# MotionBoard_Rev_C-old-sd.net
KiCad netlist of a schematic drawn in EAGLE
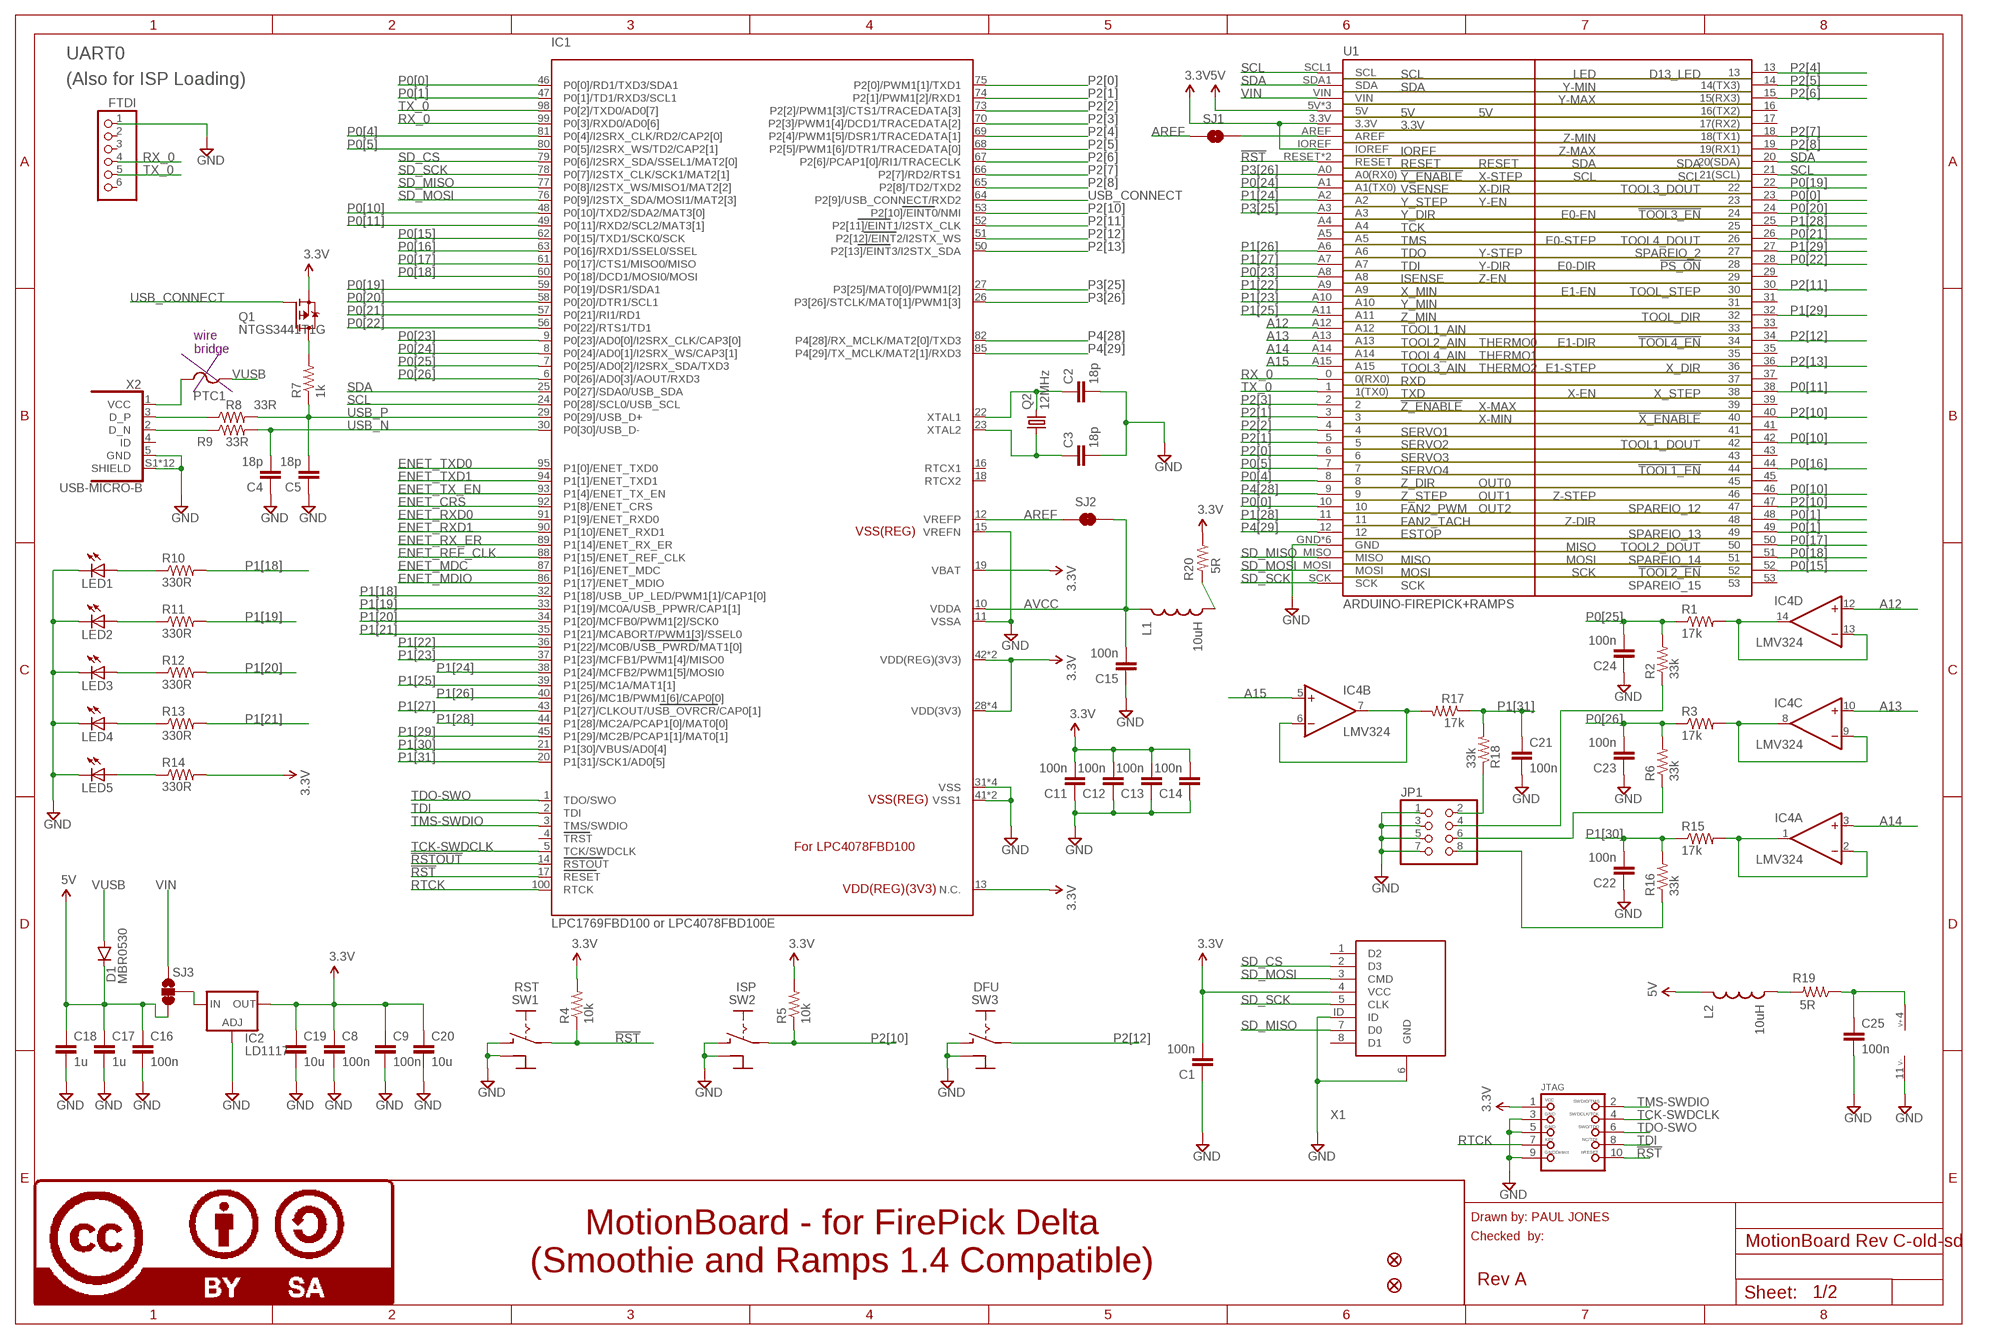
[diagram p0: schematic, sheet 1]
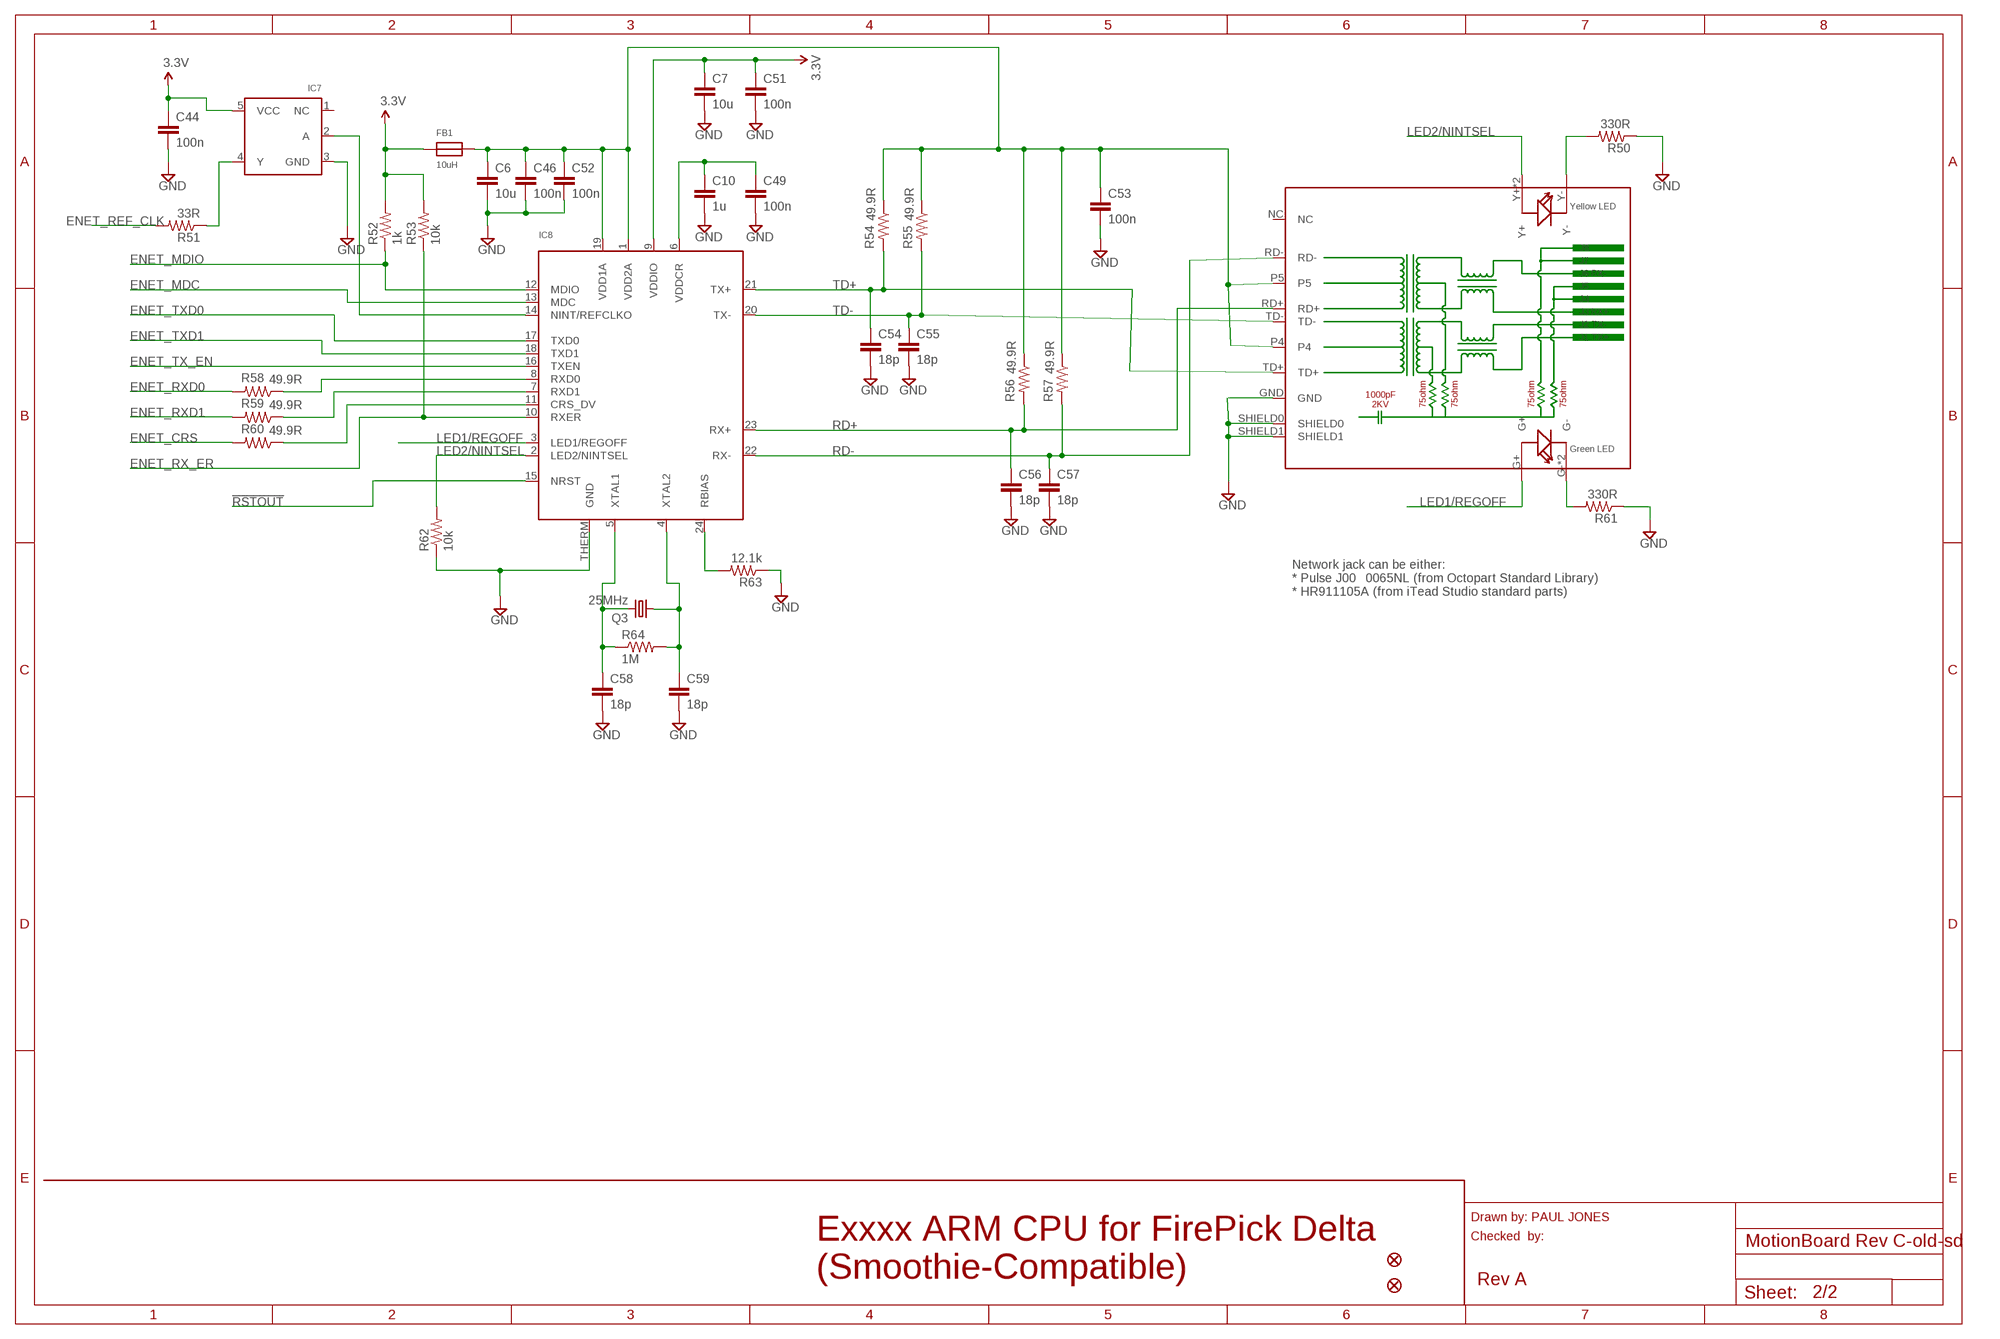
[diagram p1: schematic, sheet 2]

(export (version "E")
  (design (tool "Eeschema 10.0.6"))
  (components
    (comp (ref "C6")
      (value "10u")
      (footprint "eagle-import:0603")
      (libsource (lib "eagle-import") (part "CAP0603"))
    )
    (comp (ref "C7")
      (value "10u")
      (footprint "eagle-import:0603")
      (libsource (lib "eagle-import") (part "CAP0603"))
    )
    (comp (ref "C10")
      (value "1u")
      (footprint "eagle-import:0603")
      (libsource (lib "eagle-import") (part "CAP0603"))
    )
    (comp (ref "C44")
      (value "100n")
      (footprint "eagle-import:0603")
      (libsource (lib "eagle-import") (part "CAP0603"))
    )
    (comp (ref "C46")
      (value "100n")
      (footprint "eagle-import:0603")
      (libsource (lib "eagle-import") (part "CAP0603"))
    )
    (comp (ref "C49")
      (value "100n")
      (footprint "eagle-import:0603")
      (libsource (lib "eagle-import") (part "CAP0603"))
    )
    (comp (ref "C51")
      (value "100n")
      (footprint "eagle-import:0603")
      (libsource (lib "eagle-import") (part "CAP0603"))
    )
    (comp (ref "C52")
      (value "100n")
      (footprint "eagle-import:0603")
      (libsource (lib "eagle-import") (part "CAP0603"))
    )
    (comp (ref "C53")
      (value "100n")
      (footprint "eagle-import:0603")
      (libsource (lib "eagle-import") (part "CAP0603"))
    )
    (comp (ref "C54")
      (value "18p")
      (footprint "eagle-import:0603")
      (libsource (lib "eagle-import") (part "CAP0603"))
    )
    (comp (ref "C55")
      (value "18p")
      (footprint "eagle-import:0603")
      (libsource (lib "eagle-import") (part "CAP0603"))
    )
    (comp (ref "C56")
      (value "18p")
      (footprint "eagle-import:0603")
      (libsource (lib "eagle-import") (part "CAP0603"))
    )
    (comp (ref "C57")
      (value "18p")
      (footprint "eagle-import:0603")
      (libsource (lib "eagle-import") (part "CAP0603"))
    )
    (comp (ref "C58")
      (value "18p")
      (footprint "eagle-import:0603")
      (libsource (lib "eagle-import") (part "CAP0603"))
    )
    (comp (ref "C59")
      (value "18p")
      (footprint "eagle-import:0603")
      (libsource (lib "eagle-import") (part "CAP0603"))
    )
    (comp (ref "FB1")
      (value "10uH")
      (footprint "eagle-import:0603")
      (libsource (lib "eagle-import") (part "FERRITE"))
    )
    (comp (ref "FID17")
      (value "FIDUCIAL1X2")
      (footprint "eagle-import:FIDUCIAL-1X2")
      (libsource (lib "eagle-import") (part "FIDUCIAL1X2"))
    )
    (comp (ref "FID18")
      (value "FIDUCIAL1X2")
      (footprint "eagle-import:FIDUCIAL-1X2")
      (libsource (lib "eagle-import") (part "FIDUCIAL1X2"))
    )
    (comp (ref "IC7")
      (value "74LVC1G04")
      (footprint "eagle-import:SOT23-5")
      (libsource (lib "eagle-import") (part "74LVC1G04"))
    )
    (comp (ref "IC8")
      (value "LAN8720")
      (footprint "eagle-import:QFN24_4MM")
      (libsource (lib "eagle-import") (part "LAN8720"))
    )
    (comp (ref "Q3")
      (value "25MHz")
      (footprint "eagle-import:HC49UP")
      (libsource (lib "eagle-import") (part "CRYSTALHC49UP"))
    )
    (comp (ref "R50")
      (value "330R")
      (footprint "eagle-import:R0603")
      (libsource (lib "eagle-import") (part "R-US_R0603"))
    )
    (comp (ref "R51")
      (value "33R")
      (footprint "eagle-import:R0603")
      (libsource (lib "eagle-import") (part "R-US_R0603"))
    )
    (comp (ref "R52")
      (value "1k")
      (footprint "eagle-import:R0603")
      (libsource (lib "eagle-import") (part "R-US_R0603"))
    )
    (comp (ref "R53")
      (value "10k")
      (footprint "eagle-import:R0603")
      (libsource (lib "eagle-import") (part "R-US_R0603"))
    )
    (comp (ref "R54")
      (value "49.9R")
      (footprint "eagle-import:R0603")
      (libsource (lib "eagle-import") (part "R-US_R0603"))
    )
    (comp (ref "R55")
      (value "49.9R")
      (footprint "eagle-import:R0603")
      (libsource (lib "eagle-import") (part "R-US_R0603"))
    )
    (comp (ref "R56")
      (value "49.9R")
      (footprint "eagle-import:R0603")
      (libsource (lib "eagle-import") (part "R-US_R0603"))
    )
    (comp (ref "R57")
      (value "49.9R")
      (footprint "eagle-import:R0603")
      (libsource (lib "eagle-import") (part "R-US_R0603"))
    )
    (comp (ref "R58")
      (value "49.9R")
      (footprint "eagle-import:R0603")
      (libsource (lib "eagle-import") (part "R-US_R0603"))
    )
    (comp (ref "R59")
      (value "49.9R")
      (footprint "eagle-import:R0603")
      (libsource (lib "eagle-import") (part "R-US_R0603"))
    )
    (comp (ref "R60")
      (value "49.9R")
      (footprint "eagle-import:R0603")
      (libsource (lib "eagle-import") (part "R-US_R0603"))
    )
    (comp (ref "R61")
      (value "330R")
      (footprint "eagle-import:R0603")
      (libsource (lib "eagle-import") (part "R-US_R0603"))
    )
    (comp (ref "R62")
      (value "10k")
      (footprint "eagle-import:R0603")
      (libsource (lib "eagle-import") (part "R-US_R0603"))
    )
    (comp (ref "R63")
      (value "12.1k")
      (footprint "eagle-import:R0603")
      (libsource (lib "eagle-import") (part "R-US_R0603"))
    )
    (comp (ref "R64")
      (value "1M")
      (footprint "eagle-import:R0603")
      (libsource (lib "eagle-import") (part "R-US_R0603"))
    )
    (comp (ref "RJ1")
      (value "HR911105A")
      (footprint "eagle-import:HR911105A")
      (libsource (lib "eagle-import") (part "HR911105A"))
    )
    (comp (ref "C1")
      (value "100n")
      (footprint "eagle-import:0603")
      (libsource (lib "eagle-import") (part "CAP0603"))
    )
    (comp (ref "C2")
      (value "18p")
      (footprint "eagle-import:0603")
      (libsource (lib "eagle-import") (part "CAP0603"))
    )
    (comp (ref "C3")
      (value "18p")
      (footprint "eagle-import:0603")
      (libsource (lib "eagle-import") (part "CAP0603"))
    )
    (comp (ref "C4")
      (value "18p")
      (footprint "eagle-import:0603")
      (libsource (lib "eagle-import") (part "CAP0603"))
    )
    (comp (ref "C5")
      (value "18p")
      (footprint "eagle-import:0603")
      (libsource (lib "eagle-import") (part "CAP0603"))
    )
    (comp (ref "C8")
      (value "100n")
      (footprint "eagle-import:0603")
      (libsource (lib "eagle-import") (part "CAP0603"))
    )
    (comp (ref "C9")
      (value "100n")
      (footprint "eagle-import:0603")
      (libsource (lib "eagle-import") (part "CAP0603"))
    )
    (comp (ref "C11")
      (value "100n")
      (footprint "eagle-import:0603")
      (libsource (lib "eagle-import") (part "CAP0603"))
    )
    (comp (ref "C12")
      (value "100n")
      (footprint "eagle-import:0603")
      (libsource (lib "eagle-import") (part "CAP0603"))
    )
    (comp (ref "C13")
      (value "100n")
      (footprint "eagle-import:0603")
      (libsource (lib "eagle-import") (part "CAP0603"))
    )
    (comp (ref "C14")
      (value "100n")
      (footprint "eagle-import:0603")
      (libsource (lib "eagle-import") (part "CAP0603"))
    )
    (comp (ref "C15")
      (value "100n")
      (footprint "eagle-import:0603")
      (libsource (lib "eagle-import") (part "CAP0603"))
    )
    (comp (ref "C16")
      (value "100n")
      (footprint "eagle-import:0603")
      (libsource (lib "eagle-import") (part "CAP0603"))
    )
    (comp (ref "C17")
      (value "1u")
      (footprint "eagle-import:0603")
      (libsource (lib "eagle-import") (part "CAP0603"))
    )
    (comp (ref "C18")
      (value "1u")
      (footprint "eagle-import:0603")
      (libsource (lib "eagle-import") (part "CAP0603"))
    )
    (comp (ref "C19")
      (value "10u")
      (footprint "eagle-import:0603")
      (libsource (lib "eagle-import") (part "CAP0603"))
    )
    (comp (ref "C20")
      (value "10u")
      (footprint "eagle-import:0603")
      (libsource (lib "eagle-import") (part "CAP0603"))
    )
    (comp (ref "C21")
      (value "100n")
      (footprint "eagle-import:0603")
      (libsource (lib "eagle-import") (part "CAP0603"))
    )
    (comp (ref "C22")
      (value "100n")
      (footprint "eagle-import:0603")
      (libsource (lib "eagle-import") (part "CAP0603"))
    )
    (comp (ref "C23")
      (value "100n")
      (footprint "eagle-import:0603")
      (libsource (lib "eagle-import") (part "CAP0603"))
    )
    (comp (ref "C24")
      (value "100n")
      (footprint "eagle-import:0603")
      (libsource (lib "eagle-import") (part "CAP0603"))
    )
    (comp (ref "C25")
      (value "100n")
      (footprint "eagle-import:0603")
      (libsource (lib "eagle-import") (part "CAP0603"))
    )
    (comp (ref "D1")
      (value "MBR0530")
      (footprint "eagle-import:SOD-123")
      (libsource (lib "eagle-import") (part "DIODESOD123"))
    )
    (comp (ref "DFU")
      (value "SW3")
      (footprint "eagle-import:TOGGLE-SW-SMD")
      (libsource (lib "eagle-import") (part "TOGGLE-SW-SMD"))
    )
    (comp (ref "FID5")
      (value "FIDUCIAL1X2")
      (footprint "eagle-import:FIDUCIAL-1X2")
      (libsource (lib "eagle-import") (part "FIDUCIAL1X2"))
    )
    (comp (ref "FID6")
      (value "FIDUCIAL1X2")
      (footprint "eagle-import:FIDUCIAL-1X2")
      (libsource (lib "eagle-import") (part "FIDUCIAL1X2"))
    )
    (comp (ref "FTDI")
      (value "PINHD-1X6")
      (footprint "eagle-import:1X06")
      (libsource (lib "eagle-import") (part "PINHD-1X6"))
    )
    (comp (ref "IC1")
      (value "LPC1769FBD100 or LPC4078FBD100E")
      (footprint "eagle-import:LQFP100")
      (libsource (lib "eagle-import") (part "LPC1768"))
    )
    (comp (ref "IC2")
      (value "LD1117")
      (footprint "eagle-import:SOT223")
      (libsource (lib "eagle-import") (part "LD117A?S12TR"))
    )
    (comp (ref "IC4")
      (value "LMV324")
      (footprint "eagle-import:SO14")
      (libsource (lib "eagle-import") (part "OPA4743UA"))
    )
    (comp (ref "ISP")
      (value "SW2")
      (footprint "eagle-import:TOGGLE-SW-SMD")
      (libsource (lib "eagle-import") (part "TOGGLE-SW-SMD"))
    )
    (comp (ref "JP1")
      (value "PINHD-2X04_2.54-SMD")
      (footprint "eagle-import:2X04SMD")
      (libsource (lib "eagle-import") (part "PINHD-2X04_2.54-SMD"))
    )
    (comp (ref "JTAG")
      (value "JTAG-CORTEXM3")
      (footprint "eagle-import:2X05_1.27MM_SMT")
      (libsource (lib "eagle-import") (part "JTAG-CORTEXM3"))
    )
    (comp (ref "L1")
      (value "10uH")
      (footprint "eagle-import:0603")
      (libsource (lib "eagle-import") (part "INDUCTOR0603"))
    )
    (comp (ref "L2")
      (value "10uH")
      (footprint "eagle-import:0603")
      (libsource (lib "eagle-import") (part "INDUCTOR0603"))
    )
    (comp (ref "LED1")
      (value "LED")
      (footprint "eagle-import:LED-1206-BOTTOM")
      (libsource (lib "eagle-import") (part "LED"))
    )
    (comp (ref "LED2")
      (value "LED")
      (footprint "eagle-import:LED-1206-BOTTOM")
      (libsource (lib "eagle-import") (part "LED"))
    )
    (comp (ref "LED3")
      (value "LED")
      (footprint "eagle-import:LED-1206-BOTTOM")
      (libsource (lib "eagle-import") (part "LED"))
    )
    (comp (ref "LED4")
      (value "LED")
      (footprint "eagle-import:LED-1206-BOTTOM")
      (libsource (lib "eagle-import") (part "LED"))
    )
    (comp (ref "LED5")
      (value "LED")
      (footprint "eagle-import:LED-1206-BOTTOM")
      (libsource (lib "eagle-import") (part "LED"))
    )
    (comp (ref "LOGO6")
      (value "LOGO-CC-BY-SAMEDIUM")
      (footprint "eagle-import:LOGO-CC-BY-SA-MEDIUM")
      (libsource (lib "eagle-import") (part "LOGO-CC-BY-SAMEDIUM"))
    )
    (comp (ref "PTC1")
      (value "PTCFUSE-1812")
      (footprint "eagle-import:1812")
      (libsource (lib "eagle-import") (part "PTCFUSE-1812"))
    )
    (comp (ref "Q1")
      (value "NTGS3441T1G")
      (footprint "eagle-import:SC74_INFINEON")
      (libsource (lib "eagle-import") (part "BSL207SP"))
    )
    (comp (ref "Q2")
      (value "12MHz")
      (footprint "eagle-import:HC49UP")
      (libsource (lib "eagle-import") (part "CRYSTALHC49UP"))
    )
    (comp (ref "R1")
      (value "17k")
      (footprint "eagle-import:0603")
      (libsource (lib "eagle-import") (part "RESISTOR0603"))
    )
    (comp (ref "R2")
      (value "33k")
      (footprint "eagle-import:0603")
      (libsource (lib "eagle-import") (part "RESISTOR0603"))
    )
    (comp (ref "R3")
      (value "17k")
      (footprint "eagle-import:0603")
      (libsource (lib "eagle-import") (part "RESISTOR0603"))
    )
    (comp (ref "R4")
      (value "10k")
      (footprint "eagle-import:R0603")
      (libsource (lib "eagle-import") (part "R-US_R0603"))
    )
    (comp (ref "R5")
      (value "10k")
      (footprint "eagle-import:R0603")
      (libsource (lib "eagle-import") (part "R-US_R0603"))
    )
    (comp (ref "R6")
      (value "33k")
      (footprint "eagle-import:0603")
      (libsource (lib "eagle-import") (part "RESISTOR0603"))
    )
    (comp (ref "R7")
      (value "1k")
      (footprint "eagle-import:R0603")
      (libsource (lib "eagle-import") (part "R-US_R0603"))
    )
    (comp (ref "R8")
      (value "33R")
      (footprint "eagle-import:R0603")
      (libsource (lib "eagle-import") (part "R-US_R0603"))
    )
    (comp (ref "R9")
      (value "33R")
      (footprint "eagle-import:R0603")
      (libsource (lib "eagle-import") (part "R-US_R0603"))
    )
    (comp (ref "R10")
      (value "330R")
      (footprint "eagle-import:R0603")
      (libsource (lib "eagle-import") (part "R-US_R0603"))
    )
    (comp (ref "R11")
      (value "330R")
      (footprint "eagle-import:R0603")
      (libsource (lib "eagle-import") (part "R-US_R0603"))
    )
    (comp (ref "R12")
      (value "330R")
      (footprint "eagle-import:R0603")
      (libsource (lib "eagle-import") (part "R-US_R0603"))
    )
    (comp (ref "R13")
      (value "330R")
      (footprint "eagle-import:R0603")
      (libsource (lib "eagle-import") (part "R-US_R0603"))
    )
    (comp (ref "R14")
      (value "330R")
      (footprint "eagle-import:R0603")
      (libsource (lib "eagle-import") (part "R-US_R0603"))
    )
    (comp (ref "R15")
      (value "17k")
      (footprint "eagle-import:0603")
      (libsource (lib "eagle-import") (part "RESISTOR0603"))
    )
    (comp (ref "R16")
      (value "33k")
      (footprint "eagle-import:0603")
      (libsource (lib "eagle-import") (part "RESISTOR0603"))
    )
    (comp (ref "R17")
      (value "17k")
      (footprint "eagle-import:0603")
      (libsource (lib "eagle-import") (part "RESISTOR0603"))
    )
    (comp (ref "R18")
      (value "33k")
      (footprint "eagle-import:0603")
      (libsource (lib "eagle-import") (part "RESISTOR0603"))
    )
    (comp (ref "R19")
      (value "5R")
      (footprint "eagle-import:0603")
      (libsource (lib "eagle-import") (part "RESISTOR0603"))
    )
    (comp (ref "R20")
      (value "5R")
      (footprint "eagle-import:0603")
      (libsource (lib "eagle-import") (part "RESISTOR0603"))
    )
    (comp (ref "RST")
      (value "SW1")
      (footprint "eagle-import:TOGGLE-SW-SMD")
      (libsource (lib "eagle-import") (part "TOGGLE-SW-SMD"))
    )
    (comp (ref "SJ1")
      (value "JUMPER-PAD-2-NOYES_SILK")
      (footprint "eagle-import:PAD-JUMPER-2-NO_YES_SILK")
      (libsource (lib "eagle-import") (part "JUMPER-PAD-2-NOYES_SILK"))
    )
    (comp (ref "SJ2")
      (value "JUMPER-PAD-2-NC_BY_TRACE")
      (footprint "eagle-import:PAD-JUMPER-2-NC_BY_TRACE_YES_SILK")
      (libsource (lib "eagle-import") (part "JUMPER-PAD-2-NC_BY_TRACE"))
    )
    (comp (ref "SJ3")
      (value "JUMPER-PAD-3-2OF3_NC_BY_TRACE_SMALL")
      (footprint "eagle-import:PAD-JUMPER-3-2OF3_NC_BY_TRACE_YES_SILK_FULL_BOX")
      (libsource (lib "eagle-import") (part "JUMPER-PAD-3-2OF3_NC_BY_TRACE_SMALL"))
    )
    (comp (ref "U1")
      (value "ARDUINO-FIREPICK+RAMPS")
      (footprint "eagle-import:ARDUINO_MEGA_NEW")
      (libsource (lib "eagle-import") (part "ARDUINO-FIREPICK+RAMPS"))
    )
    (comp (ref "X1")
      (value "ST9S008V4AR1500")
      (footprint "eagle-import:ST9S008V4AR1500")
      (libsource (lib "eagle-import") (part "ST9S008V4AR1500"))
    )
    (comp (ref "X2")
      (value "USB-MICRO-B")
      (footprint "eagle-import:FCI-10118194-0001LF")
      (libsource (lib "eagle-import") (part "USB-MICRO-B"))
    )
  )
  (nets
    (net (code "1") (name "3.3V") (class "Default")
      (node (ref "C1") (pin "2") (pinfunction "2_2") (pintype "passive"))
      (node (ref "C11") (pin "2") (pinfunction "2_2") (pintype "passive"))
      (node (ref "C12") (pin "2") (pinfunction "2_2") (pintype "passive"))
      (node (ref "C13") (pin "2") (pinfunction "2_2") (pintype "passive"))
      (node (ref "C14") (pin "2") (pinfunction "2_2") (pintype "passive"))
      (node (ref "C19") (pin "1") (pinfunction "1_1") (pintype "passive"))
      (node (ref "C20") (pin "1") (pinfunction "1_1") (pintype "passive"))
      (node (ref "C44") (pin "1") (pinfunction "1_1") (pintype "passive"))
      (node (ref "C51") (pin "1") (pinfunction "1_1") (pintype "passive"))
      (node (ref "C7") (pin "1") (pinfunction "1_1") (pintype "passive"))
      (node (ref "C8") (pin "1") (pinfunction "1_1") (pintype "passive"))
      (node (ref "C9") (pin "1") (pinfunction "1_1") (pintype "passive"))
      (node (ref "FB1") (pin "1") (pinfunction "P$1_1") (pintype "bidirectional"))
      (node (ref "IC1") (pin "13") (pinfunction "N.C._13") (pintype "bidirectional"))
      (node (ref "IC1") (pin "19") (pinfunction "VBAT_19") (pintype "bidirectional"))
      (node (ref "IC1") (pin "28") (pinfunction "VDD(3V3)_28") (pintype "bidirectional"))
      (node (ref "IC1") (pin "42") (pinfunction "VDD(REG)(3V3)_42") (pintype "bidirectional"))
      (node (ref "IC1") (pin "54") (pinfunction "VDD(3V3)_54") (pintype "bidirectional"))
      (node (ref "IC1") (pin "71") (pinfunction "VDD(3V3)_71") (pintype "bidirectional"))
      (node (ref "IC1") (pin "84") (pinfunction "VDD(REG)(3V3)_84") (pintype "bidirectional"))
      (node (ref "IC1") (pin "96") (pinfunction "VDD(3V3)_96") (pintype "bidirectional"))
      (node (ref "IC2") (pin "4") (pinfunction "OUT_4") (pintype "passive"))
      (node (ref "IC7") (pin "5") (pinfunction "VCC_5") (pintype "power_in"))
      (node (ref "IC8") (pin "9") (pinfunction "VDDIO_9") (pintype "bidirectional"))
      (node (ref "JTAG") (pin "1") (pinfunction "1_1") (pintype "passive"))
      (node (ref "Q1") (pin "4") (pinfunction "S_4") (pintype "passive"))
      (node (ref "R14") (pin "2") (pinfunction "2_2") (pintype "passive"))
      (node (ref "R20") (pin "1") (pinfunction "1_1") (pintype "passive"))
      (node (ref "R4") (pin "2") (pinfunction "2_2") (pintype "passive"))
      (node (ref "R5") (pin "2") (pinfunction "2_2") (pintype "passive"))
      (node (ref "R52") (pin "2") (pinfunction "2_2") (pintype "passive"))
      (node (ref "R53") (pin "2") (pinfunction "2_2") (pintype "passive"))
      (node (ref "U1") (pin "3.3V") (pinfunction "3.3V_3.3V") (pintype "bidirectional"))
      (node (ref "U1") (pin "IOREF") (pinfunction "IOREF_IOREF") (pintype "bidirectional"))
      (node (ref "X1") (pin "4") (pinfunction "VCC_4") (pintype "input"))
    )
    (net (code "2") (name "5V") (class "Default")
      (node (ref "C16") (pin "1") (pinfunction "1_1") (pintype "passive"))
      (node (ref "C17") (pin "1") (pinfunction "1_1") (pintype "passive"))
      (node (ref "C18") (pin "1") (pinfunction "1_1") (pintype "passive"))
      (node (ref "D1") (pin "C") (pinfunction "C_C") (pintype "passive"))
      (node (ref "L2") (pin "1") (pinfunction "1_1") (pintype "passive"))
      (node (ref "SJ3") (pin "3") (pinfunction "3_3") (pintype "passive"))
      (node (ref "U1") (pin "5V") (pinfunction "5V_5V") (pintype "bidirectional"))
      (node (ref "U1") (pin "5V@1") (pinfunction "5V_5V@1") (pintype "bidirectional"))
      (node (ref "U1") (pin "5V@2") (pinfunction "5V_5V@2") (pintype "bidirectional"))
    )
    (net (code "3") (name "A12") (class "Default")
      (node (ref "IC4") (pin "12") (pinfunction "+IN_12") (pintype "input"))
      (node (ref "U1") (pin "A12") (pinfunction "A12_A12") (pintype "bidirectional"))
    )
    (net (code "4") (name "A13") (class "Default")
      (node (ref "IC4") (pin "10") (pinfunction "+IN_10") (pintype "input"))
      (node (ref "U1") (pin "A13") (pinfunction "A13_A13") (pintype "bidirectional"))
    )
    (net (code "5") (name "A14") (class "Default")
      (node (ref "IC4") (pin "3") (pinfunction "+IN_3") (pintype "input"))
      (node (ref "U1") (pin "A14") (pinfunction "A14_A14") (pintype "bidirectional"))
    )
    (net (code "6") (name "A15") (class "Default")
      (node (ref "IC4") (pin "5") (pinfunction "+IN_5") (pintype "input"))
      (node (ref "U1") (pin "A15") (pinfunction "A15_A15") (pintype "bidirectional"))
    )
    (net (code "7") (name "AREF") (class "Default")
      (node (ref "IC1") (pin "12") (pinfunction "VREFP_12") (pintype "bidirectional"))
      (node (ref "SJ1") (pin "1") (pinfunction "1_1") (pintype "passive"))
      (node (ref "SJ2") (pin "1") (pinfunction "1_1") (pintype "passive"))
    )
    (net (code "8") (name "AVCC") (class "Default")
      (node (ref "C15") (pin "2") (pinfunction "2_2") (pintype "passive"))
      (node (ref "IC1") (pin "10") (pinfunction "VDDA_10") (pintype "bidirectional"))
      (node (ref "L1") (pin "1") (pinfunction "1_1") (pintype "passive"))
      (node (ref "SJ2") (pin "2") (pinfunction "2_2") (pintype "passive"))
    )
    (net (code "9") (name "ENET_CRS") (class "Default")
      (node (ref "IC1") (pin "92") (pinfunction "P1[8]/ENET_CRS_92") (pintype "bidirectional"))
      (node (ref "R60") (pin "2") (pinfunction "2_2") (pintype "passive"))
    )
    (net (code "10") (name "ENET_MDC") (class "Default")
      (node (ref "IC1") (pin "87") (pinfunction "P1[16]/ENET_MDC_87") (pintype "bidirectional"))
      (node (ref "IC8") (pin "13") (pinfunction "MDC_13") (pintype "bidirectional"))
    )
    (net (code "11") (name "ENET_MDIO") (class "Default")
      (node (ref "IC1") (pin "86") (pinfunction "P1[17]/ENET_MDIO_86") (pintype "bidirectional"))
      (node (ref "IC8") (pin "12") (pinfunction "MDIO_12") (pintype "bidirectional"))
      (node (ref "R52") (pin "1") (pinfunction "1_1") (pintype "passive"))
    )
    (net (code "12") (name "ENET_REF_CLK") (class "Default")
      (node (ref "IC1") (pin "88") (pinfunction "P1[15]/ENET_REF_CLK_88") (pintype "bidirectional"))
      (node (ref "R51") (pin "2") (pinfunction "2_2") (pintype "passive"))
    )
    (net (code "13") (name "ENET_RXD0") (class "Default")
      (node (ref "IC1") (pin "91") (pinfunction "P1[9]/ENET_RXD0_91") (pintype "bidirectional"))
      (node (ref "R58") (pin "2") (pinfunction "2_2") (pintype "passive"))
    )
    (net (code "14") (name "ENET_RXD1") (class "Default")
      (node (ref "IC1") (pin "90") (pinfunction "P1[10]/ENET_RXD1_90") (pintype "bidirectional"))
      (node (ref "R59") (pin "2") (pinfunction "2_2") (pintype "passive"))
    )
    (net (code "15") (name "ENET_RX_ER") (class "Default")
      (node (ref "IC1") (pin "89") (pinfunction "P1[14]/ENET_RX_ER_89") (pintype "bidirectional"))
      (node (ref "IC8") (pin "10") (pinfunction "RXER_10") (pintype "bidirectional"))
      (node (ref "R53") (pin "1") (pinfunction "1_1") (pintype "passive"))
    )
    (net (code "16") (name "ENET_TXD0") (class "Default")
      (node (ref "IC1") (pin "95") (pinfunction "P1[0]/ENET_TXD0_95") (pintype "bidirectional"))
      (node (ref "IC8") (pin "17") (pinfunction "TXD0_17") (pintype "bidirectional"))
    )
    (net (code "17") (name "ENET_TXD1") (class "Default")
      (node (ref "IC1") (pin "94") (pinfunction "P1[1]/ENET_TXD1_94") (pintype "bidirectional"))
      (node (ref "IC8") (pin "18") (pinfunction "TXD1_18") (pintype "bidirectional"))
    )
    (net (code "18") (name "ENET_TX_EN") (class "Default")
      (node (ref "IC1") (pin "93") (pinfunction "P1[4]/ENET_TX_EN_93") (pintype "bidirectional"))
      (node (ref "IC8") (pin "16") (pinfunction "TXEN_16") (pintype "bidirectional"))
    )
    (net (code "19") (name "GND") (class "Default")
      (node (ref "C1") (pin "1") (pinfunction "1_1") (pintype "passive"))
      (node (ref "C10") (pin "2") (pinfunction "2_2") (pintype "passive"))
      (node (ref "C11") (pin "1") (pinfunction "1_1") (pintype "passive"))
      (node (ref "C12") (pin "1") (pinfunction "1_1") (pintype "passive"))
      (node (ref "C13") (pin "1") (pinfunction "1_1") (pintype "passive"))
      (node (ref "C14") (pin "1") (pinfunction "1_1") (pintype "passive"))
      (node (ref "C15") (pin "1") (pinfunction "1_1") (pintype "passive"))
      (node (ref "C16") (pin "2") (pinfunction "2_2") (pintype "passive"))
      (node (ref "C17") (pin "2") (pinfunction "2_2") (pintype "passive"))
      (node (ref "C18") (pin "2") (pinfunction "2_2") (pintype "passive"))
      (node (ref "C19") (pin "2") (pinfunction "2_2") (pintype "passive"))
      (node (ref "C2") (pin "2") (pinfunction "2_2") (pintype "passive"))
      (node (ref "C20") (pin "2") (pinfunction "2_2") (pintype "passive"))
      (node (ref "C21") (pin "2") (pinfunction "2_2") (pintype "passive"))
      (node (ref "C22") (pin "1") (pinfunction "1_1") (pintype "passive"))
      (node (ref "C23") (pin "1") (pinfunction "1_1") (pintype "passive"))
      (node (ref "C24") (pin "1") (pinfunction "1_1") (pintype "passive"))
      (node (ref "C25") (pin "2") (pinfunction "2_2") (pintype "passive"))
      (node (ref "C3") (pin "2") (pinfunction "2_2") (pintype "passive"))
      (node (ref "C4") (pin "1") (pinfunction "1_1") (pintype "passive"))
      (node (ref "C44") (pin "2") (pinfunction "2_2") (pintype "passive"))
      (node (ref "C46") (pin "2") (pinfunction "2_2") (pintype "passive"))
      (node (ref "C49") (pin "2") (pinfunction "2_2") (pintype "passive"))
      (node (ref "C5") (pin "1") (pinfunction "1_1") (pintype "passive"))
      (node (ref "C51") (pin "2") (pinfunction "2_2") (pintype "passive"))
      (node (ref "C52") (pin "2") (pinfunction "2_2") (pintype "passive"))
      (node (ref "C53") (pin "2") (pinfunction "2_2") (pintype "passive"))
      (node (ref "C54") (pin "2") (pinfunction "2_2") (pintype "passive"))
      (node (ref "C55") (pin "2") (pinfunction "2_2") (pintype "passive"))
      (node (ref "C56") (pin "2") (pinfunction "2_2") (pintype "passive"))
      (node (ref "C57") (pin "2") (pinfunction "2_2") (pintype "passive"))
      (node (ref "C58") (pin "2") (pinfunction "2_2") (pintype "passive"))
      (node (ref "C59") (pin "2") (pinfunction "2_2") (pintype "passive"))
      (node (ref "C6") (pin "2") (pinfunction "2_2") (pintype "passive"))
      (node (ref "C7") (pin "2") (pinfunction "2_2") (pintype "passive"))
      (node (ref "C8") (pin "2") (pinfunction "2_2") (pintype "passive"))
      (node (ref "C9") (pin "2") (pinfunction "2_2") (pintype "passive"))
      (node (ref "DFU") (pin "1") (pinfunction "C_1") (pintype "passive"))
      (node (ref "DFU") (pin "2") (pinfunction "C_2") (pintype "passive"))
      (node (ref "DFU") (pin "GND") (pinfunction "GND_GND") (pintype "passive"))
      (node (ref "FTDI") (pin "1") (pinfunction "1_1") (pintype "passive"))
      (node (ref "IC1") (pin "11") (pinfunction "VSSA_11") (pintype "bidirectional"))
      (node (ref "IC1") (pin "15") (pinfunction "VREFN_15") (pintype "bidirectional"))
      (node (ref "IC1") (pin "31") (pinfunction "VSS_31") (pintype "bidirectional"))
      (node (ref "IC1") (pin "41") (pinfunction "VSS1_41") (pintype "bidirectional"))
      (node (ref "IC1") (pin "55") (pinfunction "VSS_55") (pintype "bidirectional"))
      (node (ref "IC1") (pin "72") (pinfunction "VSS_72") (pintype "bidirectional"))
      (node (ref "IC1") (pin "83") (pinfunction "VSS1_83") (pintype "bidirectional"))
      (node (ref "IC1") (pin "97") (pinfunction "VSS_97") (pintype "bidirectional"))
      (node (ref "IC2") (pin "1") (pinfunction "ADJ_1") (pintype "input"))
      (node (ref "IC4") (pin "11") (pinfunction "V-_11") (pintype "power_in"))
      (node (ref "IC7") (pin "3") (pinfunction "GND_3") (pintype "power_in"))
      (node (ref "IC8") (pin "THERM") (pinfunction "GND_THERM") (pintype "bidirectional"))
      (node (ref "ISP") (pin "1") (pinfunction "C_1") (pintype "passive"))
      (node (ref "ISP") (pin "2") (pinfunction "C_2") (pintype "passive"))
      (node (ref "ISP") (pin "GND") (pinfunction "GND_GND") (pintype "passive"))
      (node (ref "JP1") (pin "1") (pinfunction "1_1") (pintype "passive"))
      (node (ref "JP1") (pin "3") (pinfunction "3_3") (pintype "passive"))
      (node (ref "JP1") (pin "5") (pinfunction "5_5") (pintype "passive"))
      (node (ref "JP1") (pin "7") (pinfunction "7_7") (pintype "passive"))
      (node (ref "JTAG") (pin "3") (pinfunction "3_3") (pintype "passive"))
      (node (ref "JTAG") (pin "5") (pinfunction "5_5") (pintype "passive"))
      (node (ref "JTAG") (pin "9") (pinfunction "9_9") (pintype "passive"))
      (node (ref "LED1") (pin "C") (pinfunction "C_C") (pintype "passive"))
      (node (ref "LED2") (pin "C") (pinfunction "C_C") (pintype "passive"))
      (node (ref "LED3") (pin "C") (pinfunction "C_C") (pintype "passive"))
      (node (ref "LED4") (pin "C") (pinfunction "C_C") (pintype "passive"))
      (node (ref "LED5") (pin "C") (pinfunction "C_C") (pintype "passive"))
      (node (ref "R50") (pin "1") (pinfunction "1_1") (pintype "passive"))
      (node (ref "R61") (pin "1") (pinfunction "1_1") (pintype "passive"))
      (node (ref "R62") (pin "1") (pinfunction "1_1") (pintype "passive"))
      (node (ref "R63") (pin "1") (pinfunction "1_1") (pintype "passive"))
      (node (ref "RJ1") (pin "SHIELD0") (pinfunction "SHIELD0_SHIELD0") (pintype "bidirectional"))
      (node (ref "RJ1") (pin "SHIELD1") (pinfunction "SHIELD1_SHIELD1") (pintype "bidirectional"))
      (node (ref "RST") (pin "1") (pinfunction "C_1") (pintype "passive"))
      (node (ref "RST") (pin "2") (pinfunction "C_2") (pintype "passive"))
      (node (ref "RST") (pin "GND") (pinfunction "GND_GND") (pintype "passive"))
      (node (ref "U1") (pin "GND") (pinfunction "GND_GND") (pintype "bidirectional"))
      (node (ref "U1") (pin "GND@0") (pinfunction "GND_GND@0") (pintype "bidirectional"))
      (node (ref "U1") (pin "GND@1") (pinfunction "GND_GND@1") (pintype "bidirectional"))
      (node (ref "U1") (pin "GND@2") (pinfunction "GND_GND@2") (pintype "bidirectional"))
      (node (ref "U1") (pin "GND@3") (pinfunction "GND_GND@3") (pintype "bidirectional"))
      (node (ref "U1") (pin "GNDI") (pinfunction "GND_GNDI") (pintype "bidirectional"))
      (node (ref "X1") (pin "6") (pinfunction "GND_6") (pintype "passive"))
      (node (ref "X1") (pin "ID") (pinfunction "ID_ID") (pintype "passive"))
      (node (ref "X2") (pin "5") (pinfunction "GND_5") (pintype "bidirectional"))
      (node (ref "X2") (pin "S1") (pinfunction "SHIELD_S1") (pintype "bidirectional"))
      (node (ref "X2") (pin "S10") (pinfunction "SHIELD_S10") (pintype "bidirectional"))
      (node (ref "X2") (pin "S11") (pinfunction "SHIELD_S11") (pintype "bidirectional"))
      (node (ref "X2") (pin "S12") (pinfunction "SHIELD_S12") (pintype "bidirectional"))
      (node (ref "X2") (pin "S2") (pinfunction "SHIELD_S2") (pintype "bidirectional"))
      (node (ref "X2") (pin "S3") (pinfunction "SHIELD_S3") (pintype "bidirectional"))
      (node (ref "X2") (pin "S4") (pinfunction "SHIELD_S4") (pintype "bidirectional"))
      (node (ref "X2") (pin "S5") (pinfunction "SHIELD_S5") (pintype "bidirectional"))
      (node (ref "X2") (pin "S6") (pinfunction "SHIELD_S6") (pintype "bidirectional"))
      (node (ref "X2") (pin "S7") (pinfunction "SHIELD_S7") (pintype "bidirectional"))
      (node (ref "X2") (pin "S8") (pinfunction "SHIELD_S8") (pintype "bidirectional"))
      (node (ref "X2") (pin "S9") (pinfunction "SHIELD_S9") (pintype "bidirectional"))
    )
    (net (code "20") (name "LED1{slash}REGOFF") (class "Default")
      (node (ref "IC8") (pin "3") (pinfunction "LED1/REGOFF_3") (pintype "bidirectional"))
      (node (ref "RJ1") (pin "G+") (pinfunction "G+_G+") (pintype "bidirectional"))
    )
    (net (code "21") (name "LED2{slash}NINTSEL") (class "Default")
      (node (ref "IC8") (pin "2") (pinfunction "LED2/NINTSEL_2") (pintype "bidirectional"))
      (node (ref "R62") (pin "2") (pinfunction "2_2") (pintype "passive"))
      (node (ref "RJ1") (pin "Y+") (pinfunction "Y+_Y+") (pintype "bidirectional"))
      (node (ref "RJ1") (pin "Y++") (pinfunction "Y+_Y++") (pintype "bidirectional"))
    )
    (net (code "22") (name "Net-(FB1-P$2)") (class "Default")
      (node (ref "C46") (pin "1") (pinfunction "1_1") (pintype "passive"))
      (node (ref "C52") (pin "1") (pinfunction "1_1") (pintype "passive"))
      (node (ref "C53") (pin "1") (pinfunction "1_1") (pintype "passive"))
      (node (ref "C6") (pin "1") (pinfunction "1_1") (pintype "passive"))
      (node (ref "FB1") (pin "2") (pinfunction "P$2_2") (pintype "bidirectional"))
      (node (ref "IC8") (pin "1") (pinfunction "VDD2A_1") (pintype "bidirectional"))
      (node (ref "IC8") (pin "19") (pinfunction "VDD1A_19") (pintype "bidirectional"))
      (node (ref "R54") (pin "1") (pinfunction "1_1") (pintype "passive"))
      (node (ref "R55") (pin "1") (pinfunction "1_1") (pintype "passive"))
      (node (ref "R56") (pin "1") (pinfunction "1_1") (pintype "passive"))
      (node (ref "R57") (pin "1") (pinfunction "1_1") (pintype "passive"))
      (node (ref "RJ1") (pin "P4") (pinfunction "P4_P4") (pintype "bidirectional"))
      (node (ref "RJ1") (pin "P5") (pinfunction "P5_P5") (pintype "bidirectional"))
    )
    (net (code "23") (name "Net-(IC1-XTAL1)") (class "Default")
      (node (ref "C2") (pin "1") (pinfunction "1_1") (pintype "passive"))
      (node (ref "IC1") (pin "22") (pinfunction "XTAL1_22") (pintype "bidirectional"))
      (node (ref "Q2") (pin "2") (pinfunction "2_2") (pintype "passive"))
    )
    (net (code "24") (name "Net-(IC1-XTAL2)") (class "Default")
      (node (ref "C3") (pin "1") (pinfunction "1_1") (pintype "passive"))
      (node (ref "IC1") (pin "23") (pinfunction "XTAL2_23") (pintype "bidirectional"))
      (node (ref "Q2") (pin "1") (pinfunction "1_1") (pintype "passive"))
    )
    (net (code "25") (name "Net-(IC2-IN)") (class "Default")
      (node (ref "IC2") (pin "3") (pinfunction "IN_3") (pintype "input"))
      (node (ref "SJ3") (pin "2") (pinfunction "2_2") (pintype "passive"))
    )
    (net (code "26") (name "Net-(IC4A--IN)") (class "Default")
      (node (ref "IC4") (pin "1") (pinfunction "OUT_1") (pintype "output"))
      (node (ref "IC4") (pin "2") (pinfunction "-IN_2") (pintype "input"))
      (node (ref "R15") (pin "2") (pinfunction "2_2") (pintype "passive"))
    )
    (net (code "27") (name "Net-(IC4B--IN)") (class "Default")
      (node (ref "IC4") (pin "6") (pinfunction "-IN_6") (pintype "input"))
      (node (ref "IC4") (pin "7") (pinfunction "OUT_7") (pintype "output"))
      (node (ref "R17") (pin "2") (pinfunction "2_2") (pintype "passive"))
    )
    (net (code "28") (name "Net-(IC4C--IN)") (class "Default")
      (node (ref "IC4") (pin "8") (pinfunction "OUT_8") (pintype "output"))
      (node (ref "IC4") (pin "9") (pinfunction "-IN_9") (pintype "input"))
      (node (ref "R3") (pin "2") (pinfunction "2_2") (pintype "passive"))
    )
    (net (code "29") (name "Net-(IC4D--IN)") (class "Default")
      (node (ref "IC4") (pin "13") (pinfunction "-IN_13") (pintype "input"))
      (node (ref "IC4") (pin "14") (pinfunction "OUT_14") (pintype "output"))
      (node (ref "R1") (pin "2") (pinfunction "2_2") (pintype "passive"))
    )
    (net (code "30") (name "Net-(IC4E-V+)") (class "Default")
      (node (ref "C25") (pin "1") (pinfunction "1_1") (pintype "passive"))
      (node (ref "IC4") (pin "4") (pinfunction "V+_4") (pintype "power_in"))
      (node (ref "R19") (pin "1") (pinfunction "1_1") (pintype "passive"))
    )
    (net (code "31") (name "Net-(IC7-A)") (class "Default")
      (node (ref "IC7") (pin "2") (pinfunction "A_2") (pintype "bidirectional"))
      (node (ref "IC8") (pin "14") (pinfunction "NINT/REFCLKO_14") (pintype "bidirectional"))
    )
    (net (code "32") (name "Net-(IC7-Y)") (class "Default")
      (node (ref "IC7") (pin "4") (pinfunction "Y_4") (pintype "bidirectional"))
      (node (ref "R51") (pin "1") (pinfunction "1_1") (pintype "passive"))
    )
    (net (code "33") (name "Net-(IC8-CRS_DV)") (class "Default")
      (node (ref "IC8") (pin "11") (pinfunction "CRS_DV_11") (pintype "bidirectional"))
      (node (ref "R60") (pin "1") (pinfunction "1_1") (pintype "passive"))
    )
    (net (code "34") (name "Net-(IC8-RBIAS)") (class "Default")
      (node (ref "IC8") (pin "24") (pinfunction "RBIAS_24") (pintype "bidirectional"))
      (node (ref "R63") (pin "2") (pinfunction "2_2") (pintype "passive"))
    )
    (net (code "35") (name "Net-(IC8-RXD0)") (class "Default")
      (node (ref "IC8") (pin "8") (pinfunction "RXD0_8") (pintype "bidirectional"))
      (node (ref "R58") (pin "1") (pinfunction "1_1") (pintype "passive"))
    )
    (net (code "36") (name "Net-(IC8-RXD1)") (class "Default")
      (node (ref "IC8") (pin "7") (pinfunction "RXD1_7") (pintype "bidirectional"))
      (node (ref "R59") (pin "1") (pinfunction "1_1") (pintype "passive"))
    )
    (net (code "37") (name "Net-(IC8-VDDCR)") (class "Default")
      (node (ref "C10") (pin "1") (pinfunction "1_1") (pintype "passive"))
      (node (ref "C49") (pin "1") (pinfunction "1_1") (pintype "passive"))
      (node (ref "IC8") (pin "6") (pinfunction "VDDCR_6") (pintype "bidirectional"))
    )
    (net (code "38") (name "Net-(IC8-XTAL1)") (class "Default")
      (node (ref "C58") (pin "1") (pinfunction "1_1") (pintype "passive"))
      (node (ref "IC8") (pin "5") (pinfunction "XTAL1_5") (pintype "bidirectional"))
      (node (ref "Q3") (pin "2") (pinfunction "2_2") (pintype "passive"))
      (node (ref "R64") (pin "1") (pinfunction "1_1") (pintype "passive"))
    )
    (net (code "39") (name "Net-(IC8-XTAL2)") (class "Default")
      (node (ref "C59") (pin "1") (pinfunction "1_1") (pintype "passive"))
      (node (ref "IC8") (pin "4") (pinfunction "XTAL2_4") (pintype "bidirectional"))
      (node (ref "Q3") (pin "1") (pinfunction "1_1") (pintype "passive"))
      (node (ref "R64") (pin "2") (pinfunction "2_2") (pintype "passive"))
    )
    (net (code "40") (name "Net-(JP1-Pad2)") (class "Default")
      (node (ref "JP1") (pin "2") (pinfunction "2_2") (pintype "passive"))
      (node (ref "R18") (pin "1") (pinfunction "1_1") (pintype "passive"))
    )
    (net (code "41") (name "Net-(JP1-Pad4)") (class "Default")
      (node (ref "JP1") (pin "4") (pinfunction "4_4") (pintype "passive"))
      (node (ref "R2") (pin "1") (pinfunction "1_1") (pintype "passive"))
    )
    (net (code "42") (name "Net-(JP1-Pad6)") (class "Default")
      (node (ref "JP1") (pin "6") (pinfunction "6_6") (pintype "passive"))
      (node (ref "R6") (pin "1") (pinfunction "1_1") (pintype "passive"))
    )
    (net (code "43") (name "Net-(JP1-Pad8)") (class "Default")
      (node (ref "JP1") (pin "8") (pinfunction "8_8") (pintype "passive"))
      (node (ref "R16") (pin "1") (pinfunction "1_1") (pintype "passive"))
    )
    (net (code "44") (name "Net-(L1-Pad2)") (class "Default")
      (node (ref "L1") (pin "2") (pinfunction "2_2") (pintype "passive"))
      (node (ref "R20") (pin "2") (pinfunction "2_2") (pintype "passive"))
    )
    (net (code "45") (name "Net-(L2-Pad2)") (class "Default")
      (node (ref "L2") (pin "2") (pinfunction "2_2") (pintype "passive"))
      (node (ref "R19") (pin "2") (pinfunction "2_2") (pintype "passive"))
    )
    (net (code "46") (name "Net-(LED1-PadA)") (class "Default")
      (node (ref "LED1") (pin "A") (pinfunction "A_A") (pintype "passive"))
      (node (ref "R10") (pin "1") (pinfunction "1_1") (pintype "passive"))
    )
    (net (code "47") (name "Net-(LED2-PadA)") (class "Default")
      (node (ref "LED2") (pin "A") (pinfunction "A_A") (pintype "passive"))
      (node (ref "R11") (pin "1") (pinfunction "1_1") (pintype "passive"))
    )
    (net (code "48") (name "Net-(LED3-PadA)") (class "Default")
      (node (ref "LED3") (pin "A") (pinfunction "A_A") (pintype "passive"))
      (node (ref "R12") (pin "1") (pinfunction "1_1") (pintype "passive"))
    )
    (net (code "49") (name "Net-(LED4-PadA)") (class "Default")
      (node (ref "LED4") (pin "A") (pinfunction "A_A") (pintype "passive"))
      (node (ref "R13") (pin "1") (pinfunction "1_1") (pintype "passive"))
    )
    (net (code "50") (name "Net-(LED5-PadA)") (class "Default")
      (node (ref "LED5") (pin "A") (pinfunction "A_A") (pintype "passive"))
      (node (ref "R14") (pin "1") (pinfunction "1_1") (pintype "passive"))
    )
    (net (code "51") (name "Net-(Q1-D-Pad1)") (class "Default")
      (node (ref "Q1") (pin "1") (pinfunction "D_1") (pintype "passive"))
      (node (ref "Q1") (pin "2") (pinfunction "D_2") (pintype "passive"))
      (node (ref "Q1") (pin "5") (pinfunction "D_5") (pintype "passive"))
      (node (ref "Q1") (pin "6") (pinfunction "D_6") (pintype "passive"))
      (node (ref "R7") (pin "2") (pinfunction "2_2") (pintype "passive"))
    )
    (net (code "52") (name "Net-(R50-Pad2)") (class "Default")
      (node (ref "R50") (pin "2") (pinfunction "2_2") (pintype "passive"))
      (node (ref "RJ1") (pin "Y-") (pinfunction "Y-_Y-") (pintype "bidirectional"))
    )
    (net (code "53") (name "Net-(R61-Pad2)") (class "Default")
      (node (ref "R61") (pin "2") (pinfunction "2_2") (pintype "passive"))
      (node (ref "RJ1") (pin "G-") (pinfunction "G-_G-") (pintype "bidirectional"))
      (node (ref "RJ1") (pin "G--") (pinfunction "G-_G--") (pintype "bidirectional"))
    )
    (net (code "54") (name "Net-(SJ1-Pad2)") (class "Default")
      (node (ref "SJ1") (pin "2") (pinfunction "2_2") (pintype "passive"))
      (node (ref "U1") (pin "AREF") (pinfunction "AREF_AREF") (pintype "bidirectional"))
    )
    (net (code "55") (name "Net-(X2-D_N)") (class "Default")
      (node (ref "R9") (pin "1") (pinfunction "1_1") (pintype "passive"))
      (node (ref "X2") (pin "2") (pinfunction "D_N_2") (pintype "bidirectional"))
    )
    (net (code "56") (name "Net-(X2-D_P)") (class "Default")
      (node (ref "R8") (pin "1") (pinfunction "1_1") (pintype "passive"))
      (node (ref "X2") (pin "3") (pinfunction "D_P_3") (pintype "bidirectional"))
    )
    (net (code "57") (name "Net-(X2-VCC)") (class "Default")
      (node (ref "PTC1") (pin "2") (pinfunction "2_2") (pintype "passive"))
      (node (ref "X2") (pin "1") (pinfunction "VCC_1") (pintype "bidirectional"))
    )
    (net (code "58") (name "P0[0]") (class "Default")
      (node (ref "IC1") (pin "46") (pinfunction "P0[0]/RD1/TXD3/SDA1_46") (pintype "bidirectional"))
      (node (ref "U1") (pin "10") (pinfunction "10_10") (pintype "bidirectional"))
      (node (ref "U1") (pin "23") (pinfunction "23_23") (pintype "bidirectional"))
    )
    (net (code "59") (name "P0[1]") (class "Default")
      (node (ref "IC1") (pin "47") (pinfunction "P0[1]/TD1/RXD3/SCL1_47") (pintype "bidirectional"))
      (node (ref "U1") (pin "48") (pinfunction "48_48") (pintype "bidirectional"))
      (node (ref "U1") (pin "49") (pinfunction "49_49") (pintype "bidirectional"))
    )
    (net (code "60") (name "P0[4]") (class "Default")
      (node (ref "IC1") (pin "81") (pinfunction "P0[4]/I2SRX_CLK/RD2/CAP2[0]_81") (pintype "bidirectional"))
      (node (ref "U1") (pin "8") (pinfunction "8_8") (pintype "bidirectional"))
    )
    (net (code "61") (name "P0[5]") (class "Default")
      (node (ref "IC1") (pin "80") (pinfunction "P0[5]/I2SRX_WS/TD2/CAP2[1]_80") (pintype "bidirectional"))
      (node (ref "U1") (pin "7") (pinfunction "7_7") (pintype "bidirectional"))
    )
    (net (code "62") (name "P0[10]") (class "Default")
      (node (ref "IC1") (pin "48") (pinfunction "P0[10]/TXD2/SDA2/MAT3[0]_48") (pintype "bidirectional"))
      (node (ref "U1") (pin "42") (pinfunction "42_42") (pintype "bidirectional"))
      (node (ref "U1") (pin "46") (pinfunction "46_46") (pintype "bidirectional"))
    )
    (net (code "63") (name "P0[11]") (class "Default")
      (node (ref "IC1") (pin "49") (pinfunction "P0[11]/RXD2/SCL2/MAT3[1]_49") (pintype "bidirectional"))
      (node (ref "U1") (pin "38") (pinfunction "38_38") (pintype "bidirectional"))
    )
    (net (code "64") (name "P0[15]") (class "Default")
      (node (ref "IC1") (pin "62") (pinfunction "P0[15]/TXD1/SCK0/SCK_62") (pintype "bidirectional"))
      (node (ref "U1") (pin "52") (pinfunction "52_52") (pintype "bidirectional"))
    )
    (net (code "65") (name "P0[16]") (class "Default")
      (node (ref "IC1") (pin "63") (pinfunction "P0[16]/RXD1/SSEL0/SSEL_63") (pintype "bidirectional"))
      (node (ref "U1") (pin "44") (pinfunction "44_44") (pintype "bidirectional"))
    )
    (net (code "66") (name "P0[17]") (class "Default")
      (node (ref "IC1") (pin "61") (pinfunction "P0[17]/CTS1/MISO0/MISO_61") (pintype "bidirectional"))
      (node (ref "U1") (pin "50") (pinfunction "50_50") (pintype "bidirectional"))
    )
    (net (code "67") (name "P0[18]") (class "Default")
      (node (ref "IC1") (pin "60") (pinfunction "P0[18]/DCD1/MOSI0/MOSI_60") (pintype "bidirectional"))
      (node (ref "U1") (pin "51") (pinfunction "51_51") (pintype "bidirectional"))
    )
    (net (code "68") (name "P0[19]") (class "Default")
      (node (ref "IC1") (pin "59") (pinfunction "P0[19]/DSR1/SDA1_59") (pintype "bidirectional"))
      (node (ref "U1") (pin "22") (pinfunction "22_22") (pintype "bidirectional"))
    )
    (net (code "69") (name "P0[20]") (class "Default")
      (node (ref "IC1") (pin "58") (pinfunction "P0[20]/DTR1/SCL1_58") (pintype "bidirectional"))
      (node (ref "U1") (pin "24") (pinfunction "24_24") (pintype "bidirectional"))
    )
    (net (code "70") (name "P0[21]") (class "Default")
      (node (ref "IC1") (pin "57") (pinfunction "P0[21]/RI1/RD1_57") (pintype "bidirectional"))
      (node (ref "U1") (pin "26") (pinfunction "26_26") (pintype "bidirectional"))
    )
    (net (code "71") (name "P0[22]") (class "Default")
      (node (ref "IC1") (pin "56") (pinfunction "P0[22]/RTS1/TD1_56") (pintype "bidirectional"))
      (node (ref "U1") (pin "28") (pinfunction "28_28") (pintype "bidirectional"))
    )
    (net (code "72") (name "P0[23]") (class "Default")
      (node (ref "IC1") (pin "9") (pinfunction "P0[23]/AD0[0]/I2SRX_CLK/CAP3[0]_9") (pintype "bidirectional"))
      (node (ref "U1") (pin "A8") (pinfunction "A8_A8") (pintype "bidirectional"))
    )
    (net (code "73") (name "P0[24]") (class "Default")
      (node (ref "IC1") (pin "8") (pinfunction "P0[24]/AD0[1]/I2SRX_WS/CAP3[1]_8") (pintype "bidirectional"))
      (node (ref "U1") (pin "A1") (pinfunction "A1(TX0)_A1") (pintype "bidirectional"))
    )
    (net (code "74") (name "P0[25]") (class "Default")
      (node (ref "C24") (pin "2") (pinfunction "2_2") (pintype "passive"))
      (node (ref "IC1") (pin "7") (pinfunction "P0[25]/AD0[2]/I2SRX_SDA/TXD3_7") (pintype "bidirectional"))
      (node (ref "R1") (pin "1") (pinfunction "1_1") (pintype "passive"))
      (node (ref "R2") (pin "2") (pinfunction "2_2") (pintype "passive"))
    )
    (net (code "75") (name "P0[26]") (class "Default")
      (node (ref "C23") (pin "2") (pinfunction "2_2") (pintype "passive"))
      (node (ref "IC1") (pin "6") (pinfunction "P0[26]/AD0[3]/AOUT/RXD3_6") (pintype "bidirectional"))
      (node (ref "R3") (pin "1") (pinfunction "1_1") (pintype "passive"))
      (node (ref "R6") (pin "2") (pinfunction "2_2") (pintype "passive"))
    )
    (net (code "76") (name "P1[18]") (class "Default")
      (node (ref "IC1") (pin "32") (pinfunction "P1[18]/USB_UP_LED/PWM1[1]/CAP1[0]_32") (pintype "bidirectional"))
      (node (ref "R10") (pin "2") (pinfunction "2_2") (pintype "passive"))
    )
    (net (code "77") (name "P1[19]") (class "Default")
      (node (ref "IC1") (pin "33") (pinfunction "P1[19]/MC0A/USB_PPWR/CAP1[1]_33") (pintype "bidirectional"))
      (node (ref "R11") (pin "2") (pinfunction "2_2") (pintype "passive"))
    )
    (net (code "78") (name "P1[20]") (class "Default")
      (node (ref "IC1") (pin "34") (pinfunction "P1[20]/MCFB0/PWM1[2]/SCK0_34") (pintype "bidirectional"))
      (node (ref "R12") (pin "2") (pinfunction "2_2") (pintype "passive"))
    )
    (net (code "79") (name "P1[21]") (class "Default")
      (node (ref "IC1") (pin "35") (pinfunction "P1[21]/MCABORT/PWM1[3]/SSEL0_35") (pintype "bidirectional"))
      (node (ref "R13") (pin "2") (pinfunction "2_2") (pintype "passive"))
    )
    (net (code "80") (name "P1[22]") (class "Default")
      (node (ref "IC1") (pin "36") (pinfunction "P1[22]/MC0B/USB_PWRD/MAT1[0]_36") (pintype "bidirectional"))
      (node (ref "U1") (pin "A9") (pinfunction "A9_A9") (pintype "bidirectional"))
    )
    (net (code "81") (name "P1[23]") (class "Default")
      (node (ref "IC1") (pin "37") (pinfunction "P1[23]/MCFB1/PWM1[4]/MISO0_37") (pintype "bidirectional"))
      (node (ref "U1") (pin "A10") (pinfunction "A10_A10") (pintype "bidirectional"))
    )
    (net (code "82") (name "P1[24]") (class "Default")
      (node (ref "IC1") (pin "38") (pinfunction "P1[24]/MCFB2/PWM1[5]/MOSI0_38") (pintype "bidirectional"))
      (node (ref "U1") (pin "A2") (pinfunction "A2_A2") (pintype "bidirectional"))
    )
    (net (code "83") (name "P1[25]") (class "Default")
      (node (ref "IC1") (pin "39") (pinfunction "P1[25]/MC1A/MAT1[1]_39") (pintype "bidirectional"))
      (node (ref "U1") (pin "A11") (pinfunction "A11_A11") (pintype "bidirectional"))
    )
    (net (code "84") (name "P1[26]") (class "Default")
      (node (ref "IC1") (pin "40") (pinfunction "P1[26]/MC1B/PWM1[6]/CAP0[0]_40") (pintype "bidirectional"))
      (node (ref "U1") (pin "A6") (pinfunction "A6_A6") (pintype "bidirectional"))
    )
    (net (code "85") (name "P1[27]") (class "Default")
      (node (ref "IC1") (pin "43") (pinfunction "P1[27]/CLKOUT/USB_OVRCR/CAP0[1]_43") (pintype "bidirectional"))
      (node (ref "U1") (pin "A7") (pinfunction "A7_A7") (pintype "bidirectional"))
    )
    (net (code "86") (name "P1[28]") (class "Default")
      (node (ref "IC1") (pin "44") (pinfunction "P1[28]/MC2A/PCAP1[0]/MAT0[0]_44") (pintype "bidirectional"))
      (node (ref "U1") (pin "11") (pinfunction "11_11") (pintype "bidirectional"))
      (node (ref "U1") (pin "25") (pinfunction "25_25") (pintype "bidirectional"))
    )
    (net (code "87") (name "P1[29]") (class "Default")
      (node (ref "IC1") (pin "45") (pinfunction "P1[29]/MC2B/PCAP1[1]/MAT0[1]_45") (pintype "bidirectional"))
      (node (ref "U1") (pin "27") (pinfunction "27_27") (pintype "bidirectional"))
      (node (ref "U1") (pin "32") (pinfunction "32_32") (pintype "bidirectional"))
    )
    (net (code "88") (name "P1[30]") (class "Default")
      (node (ref "C22") (pin "2") (pinfunction "2_2") (pintype "passive"))
      (node (ref "IC1") (pin "21") (pinfunction "P1[30]/VBUS/AD0[4]_21") (pintype "bidirectional"))
      (node (ref "R15") (pin "1") (pinfunction "1_1") (pintype "passive"))
      (node (ref "R16") (pin "2") (pinfunction "2_2") (pintype "passive"))
    )
    (net (code "89") (name "P1[31]") (class "Default")
      (node (ref "C21") (pin "1") (pinfunction "1_1") (pintype "passive"))
      (node (ref "IC1") (pin "20") (pinfunction "P1[31]/SCK1/AD0[5]_20") (pintype "bidirectional"))
      (node (ref "R17") (pin "1") (pinfunction "1_1") (pintype "passive"))
      (node (ref "R18") (pin "2") (pinfunction "2_2") (pintype "passive"))
    )
    (net (code "90") (name "P2[0]") (class "Default")
      (node (ref "IC1") (pin "75") (pinfunction "P2[0]/PWM1[1]/TXD1_75") (pintype "bidirectional"))
      (node (ref "U1") (pin "6") (pinfunction "6_6") (pintype "bidirectional"))
    )
    (net (code "91") (name "P2[1]") (class "Default")
      (node (ref "IC1") (pin "74") (pinfunction "P2[1]/PWM1[2]/RXD1_74") (pintype "bidirectional"))
      (node (ref "U1") (pin "3") (pinfunction "3_3") (pintype "bidirectional"))
      (node (ref "U1") (pin "5") (pinfunction "5_5") (pintype "bidirectional"))
    )
    (net (code "92") (name "P2[2]") (class "Default")
      (node (ref "IC1") (pin "73") (pinfunction "P2[2]/PWM1[3]/CTS1/TRACEDATA[3]_73") (pintype "bidirectional"))
      (node (ref "U1") (pin "4") (pinfunction "4_4") (pintype "bidirectional"))
    )
    (net (code "93") (name "P2[3]") (class "Default")
      (node (ref "IC1") (pin "70") (pinfunction "P2[3]/PWM1[4]/DCD1/TRACEDATA[2]_70") (pintype "bidirectional"))
      (node (ref "U1") (pin "2") (pinfunction "2_2") (pintype "bidirectional"))
    )
    (net (code "94") (name "P2[4]") (class "Default")
      (node (ref "IC1") (pin "69") (pinfunction "P2[4]/PWM1[5]/DSR1/TRACEDATA[1]_69") (pintype "bidirectional"))
      (node (ref "U1") (pin "13") (pinfunction "13_13") (pintype "bidirectional"))
    )
    (net (code "95") (name "P2[5]") (class "Default")
      (node (ref "IC1") (pin "68") (pinfunction "P2[5]/PWM1[6]/DTR1/TRACEDATA[0]_68") (pintype "bidirectional"))
      (node (ref "U1") (pin "14") (pinfunction "14(TX3)_14") (pintype "bidirectional"))
    )
    (net (code "96") (name "P2[6]") (class "Default")
      (node (ref "IC1") (pin "67") (pinfunction "P2[6]/PCAP1[0]/RI1/TRACECLK_67") (pintype "bidirectional"))
      (node (ref "U1") (pin "15") (pinfunction "15(RX3)_15") (pintype "bidirectional"))
    )
    (net (code "97") (name "P2[7]") (class "Default")
      (node (ref "IC1") (pin "66") (pinfunction "P2[7]/RD2/RTS1_66") (pintype "bidirectional"))
      (node (ref "U1") (pin "18") (pinfunction "18(TX1)_18") (pintype "bidirectional"))
    )
    (net (code "98") (name "P2[8]") (class "Default")
      (node (ref "IC1") (pin "65") (pinfunction "P2[8]/TD2/TXD2_65") (pintype "bidirectional"))
      (node (ref "U1") (pin "19") (pinfunction "19(RX1)_19") (pintype "bidirectional"))
    )
    (net (code "99") (name "P2[10]") (class "Default")
      (node (ref "IC1") (pin "53") (pinfunction "P2[10]/EINT0/NMI_53") (pintype "bidirectional"))
      (node (ref "ISP") (pin "3") (pinfunction "I_3") (pintype "passive"))
      (node (ref "ISP") (pin "4") (pinfunction "I_4") (pintype "passive"))
      (node (ref "R5") (pin "1") (pinfunction "1_1") (pintype "passive"))
      (node (ref "U1") (pin "40") (pinfunction "40_40") (pintype "bidirectional"))
      (node (ref "U1") (pin "47") (pinfunction "47_47") (pintype "bidirectional"))
    )
    (net (code "100") (name "P2[11]") (class "Default")
      (node (ref "IC1") (pin "52") (pinfunction "P2[11]/EINT1/I2STX_CLK_52") (pintype "bidirectional"))
      (node (ref "U1") (pin "30") (pinfunction "30_30") (pintype "bidirectional"))
    )
    (net (code "101") (name "P2[12]") (class "Default")
      (node (ref "DFU") (pin "3") (pinfunction "I_3") (pintype "passive"))
      (node (ref "DFU") (pin "4") (pinfunction "I_4") (pintype "passive"))
      (node (ref "IC1") (pin "51") (pinfunction "P2[12]/EINT2/I2STX_WS_51") (pintype "bidirectional"))
      (node (ref "U1") (pin "34") (pinfunction "34_34") (pintype "bidirectional"))
    )
    (net (code "102") (name "P2[13]") (class "Default")
      (node (ref "IC1") (pin "50") (pinfunction "P2[13]/EINT3/I2STX_SDA_50") (pintype "bidirectional"))
      (node (ref "U1") (pin "36") (pinfunction "36_36") (pintype "bidirectional"))
    )
    (net (code "103") (name "P3[25]") (class "Default")
      (node (ref "IC1") (pin "27") (pinfunction "P3[25]/MAT0[0]/PWM1[2]_27") (pintype "bidirectional"))
      (node (ref "U1") (pin "A3") (pinfunction "A3_A3") (pintype "bidirectional"))
    )
    (net (code "104") (name "P3[26]") (class "Default")
      (node (ref "IC1") (pin "26") (pinfunction "P3[26]/STCLK/MAT0[1]/PWM1[3]_26") (pintype "bidirectional"))
      (node (ref "U1") (pin "A0") (pinfunction "A0(RX0)_A0") (pintype "bidirectional"))
    )
    (net (code "105") (name "P4[28]") (class "Default")
      (node (ref "IC1") (pin "82") (pinfunction "P4[28]/RX_MCLK/MAT2[0]/TXD3_82") (pintype "bidirectional"))
      (node (ref "U1") (pin "9") (pinfunction "9_9") (pintype "bidirectional"))
    )
    (net (code "106") (name "P4[29]") (class "Default")
      (node (ref "IC1") (pin "85") (pinfunction "P4[29]/TX_MCLK/MAT2[1]/RXD3_85") (pintype "bidirectional"))
      (node (ref "U1") (pin "12") (pinfunction "12_12") (pintype "bidirectional"))
    )
    (net (code "107") (name "RD+") (class "Default")
      (node (ref "C56") (pin "1") (pinfunction "1_1") (pintype "passive"))
      (node (ref "IC8") (pin "23") (pinfunction "RX+_23") (pintype "bidirectional"))
      (node (ref "R56") (pin "2") (pinfunction "2_2") (pintype "passive"))
      (node (ref "RJ1") (pin "RD+") (pinfunction "RD+_RD+") (pintype "bidirectional"))
    )
    (net (code "108") (name "RD-") (class "Default")
      (node (ref "C57") (pin "1") (pinfunction "1_1") (pintype "passive"))
      (node (ref "IC8") (pin "22") (pinfunction "RX-_22") (pintype "bidirectional"))
      (node (ref "R57") (pin "2") (pinfunction "2_2") (pintype "passive"))
      (node (ref "RJ1") (pin "RD-") (pinfunction "RD-_RD-") (pintype "bidirectional"))
    )
    (net (code "109") (name "RTCK") (class "Default")
      (node (ref "IC1") (pin "100") (pinfunction "RTCK_100") (pintype "bidirectional"))
      (node (ref "JTAG") (pin "7") (pinfunction "7_7") (pintype "passive"))
    )
    (net (code "110") (name "RX_0") (class "Default")
      (node (ref "FTDI") (pin "4") (pinfunction "4_4") (pintype "passive"))
      (node (ref "IC1") (pin "99") (pinfunction "P0[3]/RXD0/AD0[6]_99") (pintype "bidirectional"))
      (node (ref "U1") (pin "0") (pinfunction "0(RX0)_0") (pintype "bidirectional"))
    )
    (net (code "111") (name "SCL") (class "Default")
      (node (ref "IC1") (pin "24") (pinfunction "P0[28]/SCL0/USB_SCL_24") (pintype "bidirectional"))
      (node (ref "U1") (pin "21") (pinfunction "21(SCL)_21") (pintype "bidirectional"))
      (node (ref "U1") (pin "SCL1") (pinfunction "SCL_SCL1") (pintype "bidirectional"))
    )
    (net (code "112") (name "SDA") (class "Default")
      (node (ref "IC1") (pin "25") (pinfunction "P0[27]/SDA0/USB_SDA_25") (pintype "bidirectional"))
      (node (ref "U1") (pin "20") (pinfunction "20(SDA)_20") (pintype "bidirectional"))
      (node (ref "U1") (pin "SDA1") (pinfunction "SDA_SDA1") (pintype "bidirectional"))
    )
    (net (code "113") (name "SD_CS") (class "Default")
      (node (ref "IC1") (pin "79") (pinfunction "P0[6]/I2SRX_SDA/SSEL1/MAT2[0]_79") (pintype "bidirectional"))
      (node (ref "X1") (pin "2") (pinfunction "D3_2") (pintype "bidirectional"))
    )
    (net (code "114") (name "SD_MISO") (class "Default")
      (node (ref "IC1") (pin "77") (pinfunction "P0[8]/I2STX_WS/MISO1/MAT2[2]_77") (pintype "bidirectional"))
      (node (ref "U1") (pin "MISO") (pinfunction "MISO_MISO") (pintype "bidirectional"))
      (node (ref "X1") (pin "7") (pinfunction "D0_7") (pintype "bidirectional"))
    )
    (net (code "115") (name "SD_MOSI") (class "Default")
      (node (ref "IC1") (pin "76") (pinfunction "P0[9]/I2STX_SDA/MOSI1/MAT2[3]_76") (pintype "bidirectional"))
      (node (ref "U1") (pin "MOSI") (pinfunction "MOSI_MOSI") (pintype "bidirectional"))
      (node (ref "X1") (pin "3") (pinfunction "CMD_3") (pintype "bidirectional"))
    )
    (net (code "116") (name "SD_SCK") (class "Default")
      (node (ref "IC1") (pin "78") (pinfunction "P0[7]/I2STX_CLK/SCK1/MAT2[1]_78") (pintype "bidirectional"))
      (node (ref "U1") (pin "SCK") (pinfunction "SCK_SCK") (pintype "bidirectional"))
      (node (ref "X1") (pin "5") (pinfunction "CLK_5") (pintype "input"))
    )
    (net (code "117") (name "TCK-SWDCLK") (class "Default")
      (node (ref "IC1") (pin "5") (pinfunction "TCK/SWDCLK_5") (pintype "bidirectional"))
      (node (ref "JTAG") (pin "4") (pinfunction "4_4") (pintype "passive"))
    )
    (net (code "118") (name "TD+") (class "Default")
      (node (ref "C54") (pin "1") (pinfunction "1_1") (pintype "passive"))
      (node (ref "IC8") (pin "21") (pinfunction "TX+_21") (pintype "bidirectional"))
      (node (ref "R54") (pin "2") (pinfunction "2_2") (pintype "passive"))
      (node (ref "RJ1") (pin "TD+") (pinfunction "TD+_TD+") (pintype "bidirectional"))
    )
    (net (code "119") (name "TD-") (class "Default")
      (node (ref "C55") (pin "1") (pinfunction "1_1") (pintype "passive"))
      (node (ref "IC8") (pin "20") (pinfunction "TX-_20") (pintype "bidirectional"))
      (node (ref "R55") (pin "2") (pinfunction "2_2") (pintype "passive"))
      (node (ref "RJ1") (pin "TD-") (pinfunction "TD-_TD-") (pintype "bidirectional"))
    )
    (net (code "120") (name "TDI") (class "Default")
      (node (ref "IC1") (pin "2") (pinfunction "TDI_2") (pintype "bidirectional"))
      (node (ref "JTAG") (pin "8") (pinfunction "8_8") (pintype "passive"))
    )
    (net (code "121") (name "TDO-SWO") (class "Default")
      (node (ref "IC1") (pin "1") (pinfunction "TDO/SWO_1") (pintype "bidirectional"))
      (node (ref "JTAG") (pin "6") (pinfunction "6_6") (pintype "passive"))
    )
    (net (code "122") (name "TMS-SWDIO") (class "Default")
      (node (ref "IC1") (pin "3") (pinfunction "TMS/SWDIO_3") (pintype "bidirectional"))
      (node (ref "JTAG") (pin "2") (pinfunction "2_2") (pintype "passive"))
    )
    (net (code "123") (name "TX_0") (class "Default")
      (node (ref "FTDI") (pin "5") (pinfunction "5_5") (pintype "passive"))
      (node (ref "IC1") (pin "98") (pinfunction "P0[2]/TXD0/AD0[7]_98") (pintype "bidirectional"))
      (node (ref "U1") (pin "1") (pinfunction "1(TX0)_1") (pintype "bidirectional"))
    )
    (net (code "124") (name "USB_CONNECT") (class "Default")
      (node (ref "IC1") (pin "64") (pinfunction "P2[9]/USB_CONNECT/RXD2_64") (pintype "bidirectional"))
      (node (ref "Q1") (pin "3") (pinfunction "G_3") (pintype "passive"))
    )
    (net (code "125") (name "USB_N") (class "Default")
      (node (ref "C4") (pin "2") (pinfunction "2_2") (pintype "passive"))
      (node (ref "IC1") (pin "30") (pinfunction "P0[30]/USB_D-_30") (pintype "bidirectional"))
      (node (ref "R9") (pin "2") (pinfunction "2_2") (pintype "passive"))
    )
    (net (code "126") (name "USB_P") (class "Default")
      (node (ref "C5") (pin "2") (pinfunction "2_2") (pintype "passive"))
      (node (ref "IC1") (pin "29") (pinfunction "P0[29]/USB_D+_29") (pintype "bidirectional"))
      (node (ref "R7") (pin "1") (pinfunction "1_1") (pintype "passive"))
      (node (ref "R8") (pin "2") (pinfunction "2_2") (pintype "passive"))
    )
    (net (code "127") (name "VIN") (class "Default")
      (node (ref "SJ3") (pin "1") (pinfunction "1_1") (pintype "passive"))
      (node (ref "U1") (pin "VIN") (pinfunction "VIN_VIN") (pintype "bidirectional"))
    )
    (net (code "128") (name "VUSB") (class "Default")
      (node (ref "D1") (pin "A") (pinfunction "A_A") (pintype "passive"))
      (node (ref "PTC1") (pin "1") (pinfunction "1_1") (pintype "passive"))
    )
    (net (code "129") (name "unconnected-(FTDI-Pad2)") (class "Default")
      (node (ref "FTDI") (pin "2") (pinfunction "2_2") (pintype "passive"))
    )
    (net (code "130") (name "unconnected-(FTDI-Pad3)") (class "Default")
      (node (ref "FTDI") (pin "3") (pinfunction "3_3") (pintype "passive"))
    )
    (net (code "131") (name "unconnected-(FTDI-Pad6)") (class "Default")
      (node (ref "FTDI") (pin "6") (pinfunction "6_6") (pintype "passive"))
    )
    (net (code "132") (name "unconnected-(IC1-RTCX1-Pad16)") (class "Default")
      (node (ref "IC1") (pin "16") (pinfunction "RTCX1_16") (pintype "bidirectional"))
    )
    (net (code "133") (name "unconnected-(IC1-RTCX2-Pad18)") (class "Default")
      (node (ref "IC1") (pin "18") (pinfunction "RTCX2_18") (pintype "bidirectional"))
    )
    (net (code "134") (name "unconnected-(IC1-TRST-Pad4)") (class "Default")
      (node (ref "IC1") (pin "4") (pinfunction "TRST_4") (pintype "bidirectional"))
    )
    (net (code "135") (name "unconnected-(IC7-NC-Pad1)") (class "Default")
      (node (ref "IC7") (pin "1") (pinfunction "NC_1") (pintype "no_connect"))
    )
    (net (code "136") (name "unconnected-(RJ1-PadGND)") (class "Default")
      (node (ref "RJ1") (pin "GND") (pinfunction "GND_GND") (pintype "bidirectional"))
    )
    (net (code "137") (name "unconnected-(RJ1-PadNC)") (class "Default")
      (node (ref "RJ1") (pin "NC") (pinfunction "NC_NC") (pintype "bidirectional"))
    )
    (net (code "138") (name "unconnected-(U1-16(TX2)-Pad16)") (class "Default")
      (node (ref "U1") (pin "16") (pinfunction "16(TX2)_16") (pintype "bidirectional"))
    )
    (net (code "139") (name "unconnected-(U1-17(RX2)-Pad17)") (class "Default")
      (node (ref "U1") (pin "17") (pinfunction "17(RX2)_17") (pintype "bidirectional"))
    )
    (net (code "140") (name "unconnected-(U1-Pad29)") (class "Default")
      (node (ref "U1") (pin "29") (pinfunction "29_29") (pintype "bidirectional"))
    )
    (net (code "141") (name "unconnected-(U1-Pad31)") (class "Default")
      (node (ref "U1") (pin "31") (pinfunction "31_31") (pintype "bidirectional"))
    )
    (net (code "142") (name "unconnected-(U1-Pad33)") (class "Default")
      (node (ref "U1") (pin "33") (pinfunction "33_33") (pintype "bidirectional"))
    )
    (net (code "143") (name "unconnected-(U1-Pad35)") (class "Default")
      (node (ref "U1") (pin "35") (pinfunction "35_35") (pintype "bidirectional"))
    )
    (net (code "144") (name "unconnected-(U1-Pad37)") (class "Default")
      (node (ref "U1") (pin "37") (pinfunction "37_37") (pintype "bidirectional"))
    )
    (net (code "145") (name "unconnected-(U1-Pad39)") (class "Default")
      (node (ref "U1") (pin "39") (pinfunction "39_39") (pintype "bidirectional"))
    )
    (net (code "146") (name "unconnected-(U1-Pad41)") (class "Default")
      (node (ref "U1") (pin "41") (pinfunction "41_41") (pintype "bidirectional"))
    )
    (net (code "147") (name "unconnected-(U1-Pad43)") (class "Default")
      (node (ref "U1") (pin "43") (pinfunction "43_43") (pintype "bidirectional"))
    )
    (net (code "148") (name "unconnected-(U1-Pad45)") (class "Default")
      (node (ref "U1") (pin "45") (pinfunction "45_45") (pintype "bidirectional"))
    )
    (net (code "149") (name "unconnected-(U1-Pad53)") (class "Default")
      (node (ref "U1") (pin "53") (pinfunction "53_53") (pintype "bidirectional"))
    )
    (net (code "150") (name "unconnected-(U1-PadA4)") (class "Default")
      (node (ref "U1") (pin "A4") (pinfunction "A4_A4") (pintype "bidirectional"))
    )
    (net (code "151") (name "unconnected-(U1-PadA5)") (class "Default")
      (node (ref "U1") (pin "A5") (pinfunction "A5_A5") (pintype "bidirectional"))
    )
    (net (code "152") (name "unconnected-(X1-D1-Pad8)") (class "Default")
      (node (ref "X1") (pin "8") (pinfunction "D1_8") (pintype "bidirectional"))
    )
    (net (code "153") (name "unconnected-(X1-D2-Pad1)") (class "Default")
      (node (ref "X1") (pin "1") (pinfunction "D2_1") (pintype "bidirectional"))
    )
    (net (code "154") (name "unconnected-(X2-ID-Pad4)") (class "Default")
      (node (ref "X2") (pin "4") (pinfunction "ID_4") (pintype "bidirectional"))
    )
    (net (code "155") (name "~{RSTOUT}") (class "Default")
      (node (ref "IC1") (pin "14") (pinfunction "RSTOUT_14") (pintype "bidirectional"))
      (node (ref "IC8") (pin "15") (pinfunction "NRST_15") (pintype "bidirectional"))
    )
    (net (code "156") (name "~{RST}") (class "Default")
      (node (ref "IC1") (pin "17") (pinfunction "RESET_17") (pintype "bidirectional"))
      (node (ref "JTAG") (pin "10") (pinfunction "10_10") (pintype "passive"))
      (node (ref "R4") (pin "1") (pinfunction "1_1") (pintype "passive"))
      (node (ref "RST") (pin "3") (pinfunction "I_3") (pintype "passive"))
      (node (ref "RST") (pin "4") (pinfunction "I_4") (pintype "passive"))
      (node (ref "U1") (pin "RESET") (pinfunction "RESET_RESET") (pintype "bidirectional"))
      (node (ref "U1") (pin "RST") (pinfunction "RESET_RST") (pintype "bidirectional"))
    )
  )
)
